# Minimum-System.net
KiCad netlist of a schematic drawn in EAGLE
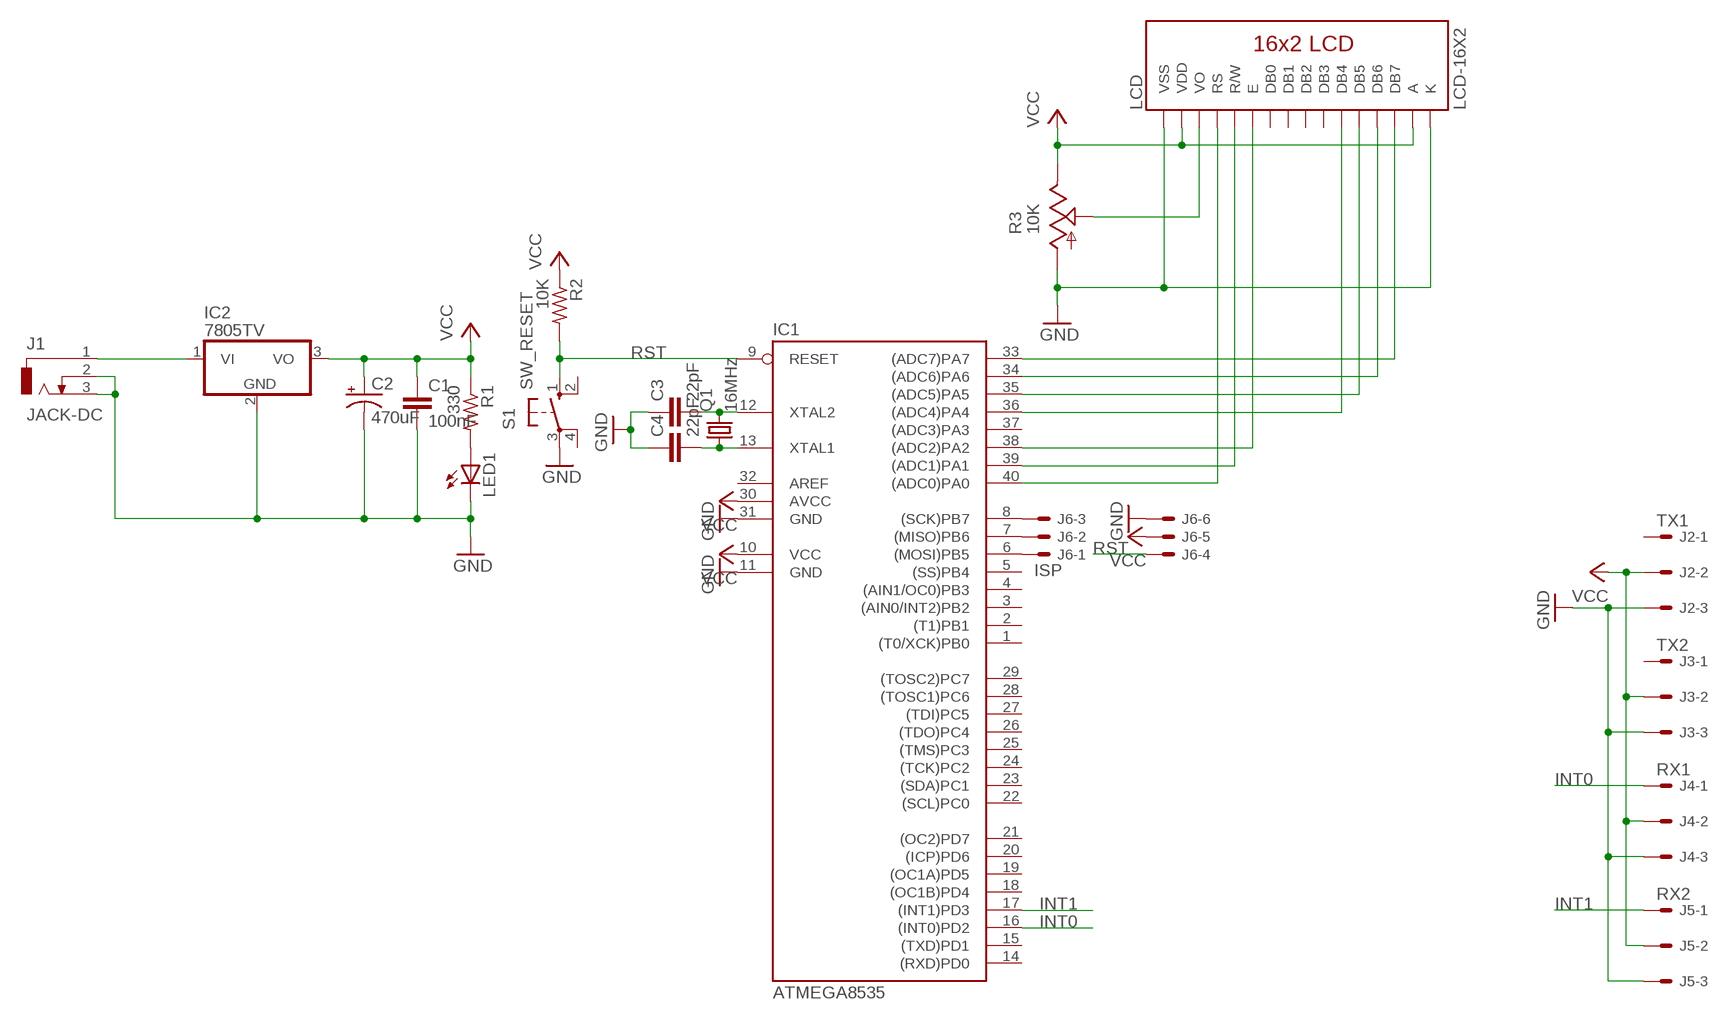
[diagram p0: schematic, sheet 1]

(export (version "E")
  (design (tool "Eeschema 10.0.6"))
  (components
    (comp (ref "C1")
      (value "100nF")
      (footprint "eagle-import:C025-024X044")
      (libsource (lib "eagle-import") (part "CAPACITOR-NONPOLAR025-024X044"))
    )
    (comp (ref "C2")
      (value "470uF")
      (footprint "eagle-import:E2,5-6")
      (libsource (lib "eagle-import") (part "CAPACITOR-POLARE2.5-6"))
    )
    (comp (ref "C3")
      (value "22pF")
      (footprint "eagle-import:C025-024X044")
      (libsource (lib "eagle-import") (part "CAPACITOR-NONPOLAR025-024X044"))
    )
    (comp (ref "C4")
      (value "22pF")
      (footprint "eagle-import:C025-024X044")
      (libsource (lib "eagle-import") (part "CAPACITOR-NONPOLAR025-024X044"))
    )
    (comp (ref "IC1")
      (value "ATMEGA8535")
      (footprint "eagle-import:DIL40")
      (fields (field (name "MPN") "ATMEGA32-16PU"))
      (libsource (lib "eagle-import") (part "ATMEGA8535/16/32"))
    )
    (comp (ref "IC2")
      (value "7805TV")
      (footprint "eagle-import:TO220V")
      (libsource (lib "eagle-import") (part "78TV05"))
    )
    (comp (ref "J1")
      (value "JACK-DC")
      (footprint "eagle-import:DCJ0202")
      (libsource (lib "eagle-import") (part "JACK-DC"))
    )
    (comp (ref "J2")
      (value "TX1")
      (footprint "eagle-import:7395-03")
      (libsource (lib "eagle-import") (part "CON_MOLEX-?-0305-7038"))
    )
    (comp (ref "J3")
      (value "TX2")
      (footprint "eagle-import:7395-03")
      (libsource (lib "eagle-import") (part "CON_MOLEX-?-0305-7038"))
    )
    (comp (ref "J4")
      (value "RX1")
      (footprint "eagle-import:7395-03")
      (libsource (lib "eagle-import") (part "CON_MOLEX-?-0305-7038"))
    )
    (comp (ref "J5")
      (value "RX2")
      (footprint "eagle-import:7395-03")
      (libsource (lib "eagle-import") (part "CON_MOLEX-?-0305-7038"))
    )
    (comp (ref "J6")
      (value "ISP")
      (footprint "eagle-import:6410-06")
      (libsource (lib "eagle-import") (part "CON_MOLEX-?-0627-2061"))
    )
    (comp (ref "LCD")
      (value "LCD-16X2")
      (footprint "eagle-import:LCD-16X2")
      (libsource (lib "eagle-import") (part "LCD-16X2"))
    )
    (comp (ref "LED1")
      (value "LED3MM")
      (footprint "eagle-import:LED3MM")
      (libsource (lib "eagle-import") (part "LED3MM"))
    )
    (comp (ref "Q1")
      (value "16MHz")
      (footprint "eagle-import:HC49_S")
      (libsource (lib "eagle-import") (part "CRYSTALHC49S"))
    )
    (comp (ref "R1")
      (value "330")
      (footprint "eagle-import:0204_7")
      (libsource (lib "eagle-import") (part "RESISTOR0204/7"))
    )
    (comp (ref "R2")
      (value "10K")
      (footprint "eagle-import:0204_7")
      (libsource (lib "eagle-import") (part "RESISTOR0204/7"))
    )
    (comp (ref "R3")
      (value "10K")
      (footprint "eagle-import:CA6V")
      (libsource (lib "eagle-import") (part "TRIMPOTCA6V"))
    )
    (comp (ref "S1")
      (value "SW_RESET")
      (footprint "eagle-import:B3F-10XX")
      (fields (field (name "MPN") "B3F-1000"))
      (libsource (lib "eagle-import") (part "SW-PUSHBUTTON"))
    )
  )
  (nets
    (net (code "1") (name "/INT0") (class "Default")
      (node (ref "IC1") (pin "16") (pinfunction "(INT0)PD2_16") (pintype "bidirectional"))
      (node (ref "J4") (pin "1") (pinfunction "S_1") (pintype "passive"))
    )
    (net (code "2") (name "/INT1") (class "Default")
      (node (ref "IC1") (pin "17") (pinfunction "(INT1)PD3_17") (pintype "bidirectional"))
      (node (ref "J5") (pin "1") (pinfunction "S_1") (pintype "passive"))
    )
    (net (code "3") (name "/RST") (class "Default")
      (node (ref "IC1") (pin "9") (pinfunction "RESET_9") (pintype "input"))
      (node (ref "J6") (pin "4") (pinfunction "S_4") (pintype "passive"))
      (node (ref "R2") (pin "2") (pinfunction "2_2") (pintype "passive"))
      (node (ref "S1") (pin "1") (pinfunction "S_1") (pintype "passive"))
    )
    (net (code "4") (name "GND") (class "Default")
      (node (ref "C1") (pin "2") (pinfunction "2_2") (pintype "passive"))
      (node (ref "C2") (pin "-") (pinfunction "-_-") (pintype "passive"))
      (node (ref "C3") (pin "1") (pinfunction "1_1") (pintype "passive"))
      (node (ref "C4") (pin "1") (pinfunction "1_1") (pintype "passive"))
      (node (ref "IC1") (pin "11") (pinfunction "GND_11") (pintype "power_in"))
      (node (ref "IC1") (pin "31") (pinfunction "GND_31") (pintype "power_in"))
      (node (ref "IC2") (pin "2") (pinfunction "GND_2") (pintype "passive"))
      (node (ref "J1") (pin "2") (pinfunction "2_2") (pintype "passive"))
      (node (ref "J1") (pin "3") (pinfunction "3_3") (pintype "passive"))
      (node (ref "J2") (pin "3") (pinfunction "S_3") (pintype "passive"))
      (node (ref "J3") (pin "3") (pinfunction "S_3") (pintype "passive"))
      (node (ref "J4") (pin "3") (pinfunction "S_3") (pintype "passive"))
      (node (ref "J5") (pin "3") (pinfunction "S_3") (pintype "passive"))
      (node (ref "J6") (pin "6") (pinfunction "S_6") (pintype "passive"))
      (node (ref "LCD") (pin "1") (pinfunction "VSS_1") (pintype "power_in"))
      (node (ref "LCD") (pin "16") (pinfunction "K_16") (pintype "power_in"))
      (node (ref "LED1") (pin "K") (pinfunction "C_K") (pintype "passive"))
      (node (ref "R3") (pin "A") (pinfunction "A_A") (pintype "passive"))
      (node (ref "S1") (pin "3") (pinfunction "P_3") (pintype "passive"))
    )
    (net (code "5") (name "Net-(IC1-(ADC0)PA0)") (class "Default")
      (node (ref "IC1") (pin "40") (pinfunction "(ADC0)PA0_40") (pintype "bidirectional"))
      (node (ref "LCD") (pin "4") (pinfunction "RS_4") (pintype "input"))
    )
    (net (code "6") (name "Net-(IC1-(ADC1)PA1)") (class "Default")
      (node (ref "IC1") (pin "39") (pinfunction "(ADC1)PA1_39") (pintype "bidirectional"))
      (node (ref "LCD") (pin "5") (pinfunction "R/W_5") (pintype "input"))
    )
    (net (code "7") (name "Net-(IC1-(ADC2)PA2)") (class "Default")
      (node (ref "IC1") (pin "38") (pinfunction "(ADC2)PA2_38") (pintype "bidirectional"))
      (node (ref "LCD") (pin "6") (pinfunction "E_6") (pintype "input"))
    )
    (net (code "8") (name "Net-(IC1-(ADC4)PA4)") (class "Default")
      (node (ref "IC1") (pin "36") (pinfunction "(ADC4)PA4_36") (pintype "bidirectional"))
      (node (ref "LCD") (pin "11") (pinfunction "DB4_11") (pintype "bidirectional"))
    )
    (net (code "9") (name "Net-(IC1-(ADC5)PA5)") (class "Default")
      (node (ref "IC1") (pin "35") (pinfunction "(ADC5)PA5_35") (pintype "bidirectional"))
      (node (ref "LCD") (pin "12") (pinfunction "DB5_12") (pintype "bidirectional"))
    )
    (net (code "10") (name "Net-(IC1-(ADC6)PA6)") (class "Default")
      (node (ref "IC1") (pin "34") (pinfunction "(ADC6)PA6_34") (pintype "bidirectional"))
      (node (ref "LCD") (pin "13") (pinfunction "DB6_13") (pintype "bidirectional"))
    )
    (net (code "11") (name "Net-(IC1-(ADC7)PA7)") (class "Default")
      (node (ref "IC1") (pin "33") (pinfunction "(ADC7)PA7_33") (pintype "bidirectional"))
      (node (ref "LCD") (pin "14") (pinfunction "DB7_14") (pintype "bidirectional"))
    )
    (net (code "12") (name "Net-(IC1-(MISO)PB6)") (class "Default")
      (node (ref "IC1") (pin "7") (pinfunction "(MISO)PB6_7") (pintype "bidirectional"))
      (node (ref "J6") (pin "2") (pinfunction "S_2") (pintype "passive"))
    )
    (net (code "13") (name "Net-(IC1-(MOSI)PB5)") (class "Default")
      (node (ref "IC1") (pin "6") (pinfunction "(MOSI)PB5_6") (pintype "bidirectional"))
      (node (ref "J6") (pin "1") (pinfunction "S_1") (pintype "passive"))
    )
    (net (code "14") (name "Net-(IC1-(SCK)PB7)") (class "Default")
      (node (ref "IC1") (pin "8") (pinfunction "(SCK)PB7_8") (pintype "bidirectional"))
      (node (ref "J6") (pin "3") (pinfunction "S_3") (pintype "passive"))
    )
    (net (code "15") (name "Net-(IC1-XTAL1)") (class "Default")
      (node (ref "C4") (pin "2") (pinfunction "2_2") (pintype "passive"))
      (node (ref "IC1") (pin "13") (pinfunction "XTAL1_13") (pintype "bidirectional"))
      (node (ref "Q1") (pin "1") (pinfunction "1_1") (pintype "passive"))
    )
    (net (code "16") (name "Net-(IC1-XTAL2)") (class "Default")
      (node (ref "C3") (pin "2") (pinfunction "2_2") (pintype "passive"))
      (node (ref "IC1") (pin "12") (pinfunction "XTAL2_12") (pintype "bidirectional"))
      (node (ref "Q1") (pin "2") (pinfunction "2_2") (pintype "passive"))
    )
    (net (code "17") (name "Net-(IC2-VI)") (class "Default")
      (node (ref "IC2") (pin "1") (pinfunction "VI_1") (pintype "input"))
      (node (ref "J1") (pin "1") (pinfunction "1_1") (pintype "passive"))
    )
    (net (code "18") (name "Net-(LCD-VO)") (class "Default")
      (node (ref "LCD") (pin "3") (pinfunction "VO_3") (pintype "bidirectional"))
      (node (ref "R3") (pin "S") (pinfunction "S_S") (pintype "passive"))
    )
    (net (code "19") (name "Net-(LED1-PadA)") (class "Default")
      (node (ref "LED1") (pin "A") (pinfunction "A_A") (pintype "passive"))
      (node (ref "R1") (pin "2") (pinfunction "2_2") (pintype "passive"))
    )
    (net (code "20") (name "VCC") (class "Default")
      (node (ref "C1") (pin "1") (pinfunction "1_1") (pintype "passive"))
      (node (ref "C2") (pin "+") (pinfunction "+_+") (pintype "passive"))
      (node (ref "IC1") (pin "10") (pinfunction "VCC_10") (pintype "power_in"))
      (node (ref "IC1") (pin "30") (pinfunction "AVCC_30") (pintype "power_in"))
      (node (ref "IC2") (pin "3") (pinfunction "VO_3") (pintype "passive"))
      (node (ref "J2") (pin "2") (pinfunction "S_2") (pintype "passive"))
      (node (ref "J3") (pin "2") (pinfunction "S_2") (pintype "passive"))
      (node (ref "J4") (pin "2") (pinfunction "S_2") (pintype "passive"))
      (node (ref "J5") (pin "2") (pinfunction "S_2") (pintype "passive"))
      (node (ref "J6") (pin "5") (pinfunction "S_5") (pintype "passive"))
      (node (ref "LCD") (pin "15") (pinfunction "A_15") (pintype "power_in"))
      (node (ref "LCD") (pin "2") (pinfunction "VDD_2") (pintype "power_in"))
      (node (ref "R1") (pin "1") (pinfunction "1_1") (pintype "passive"))
      (node (ref "R2") (pin "1") (pinfunction "1_1") (pintype "passive"))
      (node (ref "R3") (pin "E") (pinfunction "E_E") (pintype "passive"))
    )
    (net (code "21") (name "unconnected-(IC1-(ADC3)PA3-Pad37)") (class "Default")
      (node (ref "IC1") (pin "37") (pinfunction "(ADC3)PA3_37") (pintype "bidirectional"))
    )
    (net (code "22") (name "unconnected-(IC1-(AIN0{slash}INT2)PB2-Pad3)") (class "Default")
      (node (ref "IC1") (pin "3") (pinfunction "(AIN0/INT2)PB2_3") (pintype "bidirectional"))
    )
    (net (code "23") (name "unconnected-(IC1-(AIN1{slash}OC0)PB3-Pad4)") (class "Default")
      (node (ref "IC1") (pin "4") (pinfunction "(AIN1/OC0)PB3_4") (pintype "bidirectional"))
    )
    (net (code "24") (name "unconnected-(IC1-(ICP)PD6-Pad20)") (class "Default")
      (node (ref "IC1") (pin "20") (pinfunction "(ICP)PD6_20") (pintype "bidirectional"))
    )
    (net (code "25") (name "unconnected-(IC1-(OC1A)PD5-Pad19)") (class "Default")
      (node (ref "IC1") (pin "19") (pinfunction "(OC1A)PD5_19") (pintype "bidirectional"))
    )
    (net (code "26") (name "unconnected-(IC1-(OC1B)PD4-Pad18)") (class "Default")
      (node (ref "IC1") (pin "18") (pinfunction "(OC1B)PD4_18") (pintype "bidirectional"))
    )
    (net (code "27") (name "unconnected-(IC1-(OC2)PD7-Pad21)") (class "Default")
      (node (ref "IC1") (pin "21") (pinfunction "(OC2)PD7_21") (pintype "bidirectional"))
    )
    (net (code "28") (name "unconnected-(IC1-(RXD)PD0-Pad14)") (class "Default")
      (node (ref "IC1") (pin "14") (pinfunction "(RXD)PD0_14") (pintype "bidirectional"))
    )
    (net (code "29") (name "unconnected-(IC1-(SCL)PC0-Pad22)") (class "Default")
      (node (ref "IC1") (pin "22") (pinfunction "(SCL)PC0_22") (pintype "bidirectional"))
    )
    (net (code "30") (name "unconnected-(IC1-(SDA)PC1-Pad23)") (class "Default")
      (node (ref "IC1") (pin "23") (pinfunction "(SDA)PC1_23") (pintype "bidirectional"))
    )
    (net (code "31") (name "unconnected-(IC1-(SS)PB4-Pad5)") (class "Default")
      (node (ref "IC1") (pin "5") (pinfunction "(SS)PB4_5") (pintype "bidirectional"))
    )
    (net (code "32") (name "unconnected-(IC1-(T0{slash}XCK)PB0-Pad1)") (class "Default")
      (node (ref "IC1") (pin "1") (pinfunction "(T0/XCK)PB0_1") (pintype "bidirectional"))
    )
    (net (code "33") (name "unconnected-(IC1-(T1)PB1-Pad2)") (class "Default")
      (node (ref "IC1") (pin "2") (pinfunction "(T1)PB1_2") (pintype "bidirectional"))
    )
    (net (code "34") (name "unconnected-(IC1-(TCK)PC2-Pad24)") (class "Default")
      (node (ref "IC1") (pin "24") (pinfunction "(TCK)PC2_24") (pintype "bidirectional"))
    )
    (net (code "35") (name "unconnected-(IC1-(TDI)PC5-Pad27)") (class "Default")
      (node (ref "IC1") (pin "27") (pinfunction "(TDI)PC5_27") (pintype "bidirectional"))
    )
    (net (code "36") (name "unconnected-(IC1-(TDO)PC4-Pad26)") (class "Default")
      (node (ref "IC1") (pin "26") (pinfunction "(TDO)PC4_26") (pintype "bidirectional"))
    )
    (net (code "37") (name "unconnected-(IC1-(TMS)PC3-Pad25)") (class "Default")
      (node (ref "IC1") (pin "25") (pinfunction "(TMS)PC3_25") (pintype "bidirectional"))
    )
    (net (code "38") (name "unconnected-(IC1-(TOSC1)PC6-Pad28)") (class "Default")
      (node (ref "IC1") (pin "28") (pinfunction "(TOSC1)PC6_28") (pintype "bidirectional"))
    )
    (net (code "39") (name "unconnected-(IC1-(TOSC2)PC7-Pad29)") (class "Default")
      (node (ref "IC1") (pin "29") (pinfunction "(TOSC2)PC7_29") (pintype "bidirectional"))
    )
    (net (code "40") (name "unconnected-(IC1-(TXD)PD1-Pad15)") (class "Default")
      (node (ref "IC1") (pin "15") (pinfunction "(TXD)PD1_15") (pintype "bidirectional"))
    )
    (net (code "41") (name "unconnected-(IC1-AREF-Pad32)") (class "Default")
      (node (ref "IC1") (pin "32") (pinfunction "AREF_32") (pintype "passive"))
    )
    (net (code "42") (name "unconnected-(J2A-S-Pad1)") (class "Default")
      (node (ref "J2") (pin "1") (pinfunction "S_1") (pintype "passive"))
    )
    (net (code "43") (name "unconnected-(J3A-S-Pad1)") (class "Default")
      (node (ref "J3") (pin "1") (pinfunction "S_1") (pintype "passive"))
    )
    (net (code "44") (name "unconnected-(LCD-DB0-Pad7)") (class "Default")
      (node (ref "LCD") (pin "7") (pinfunction "DB0_7") (pintype "bidirectional"))
    )
    (net (code "45") (name "unconnected-(LCD-DB1-Pad8)") (class "Default")
      (node (ref "LCD") (pin "8") (pinfunction "DB1_8") (pintype "bidirectional"))
    )
    (net (code "46") (name "unconnected-(LCD-DB2-Pad9)") (class "Default")
      (node (ref "LCD") (pin "9") (pinfunction "DB2_9") (pintype "bidirectional"))
    )
    (net (code "47") (name "unconnected-(LCD-DB3-Pad10)") (class "Default")
      (node (ref "LCD") (pin "10") (pinfunction "DB3_10") (pintype "bidirectional"))
    )
    (net (code "48") (name "unconnected-(S1-P1-Pad4)") (class "Default")
      (node (ref "S1") (pin "4") (pinfunction "P1_4") (pintype "passive"))
    )
    (net (code "49") (name "unconnected-(S1-S1-Pad2)") (class "Default")
      (node (ref "S1") (pin "2") (pinfunction "S1_2") (pintype "passive"))
    )
  )
)
